# USBFX2LP_4.net
KiCad netlist of a schematic drawn in Altium Designer
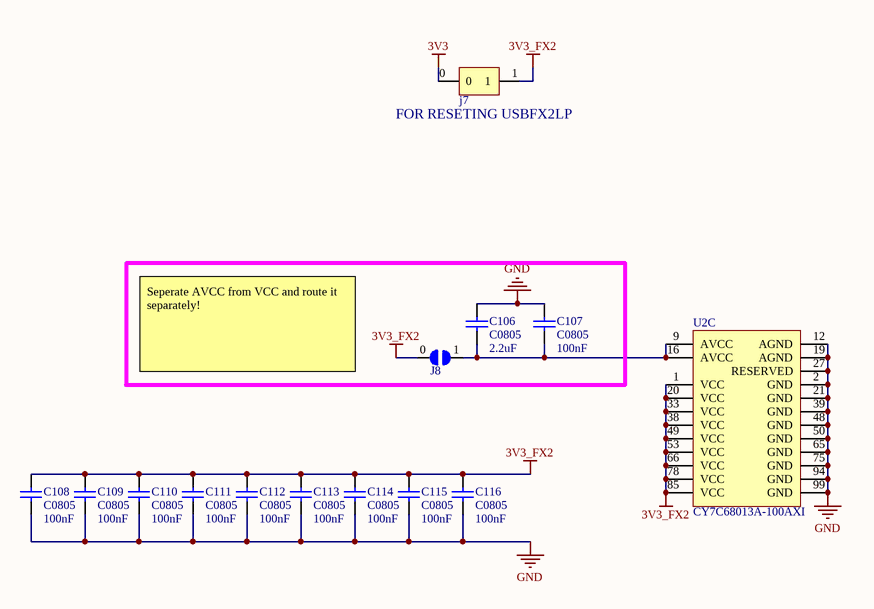
[diagram p0: USBFX2LP_4.SchDoc]

(export (version "E")
  (design (tool "Eeschema 10.0.6"))
  (components
    (comp (ref "C106")
      (value "C0805")
      (footprint "0805")
      (description "Ceramic Chip Capacitor - Standard")
      (fields (field (name "ALTIUM_VALUE") "2.2uF") (field (name "PUBLISHER") "Altium Limited"))
      (libsource (lib "KEMET Chip Capacitor") (part "C0805"))
    )
    (comp (ref "C107")
      (value "C0805")
      (footprint "0805")
      (description "Ceramic Chip Capacitor - Standard")
      (fields (field (name "ALTIUM_VALUE") "100nF") (field (name "PUBLISHER") "Altium Limited"))
      (libsource (lib "KEMET Chip Capacitor") (part "C0805"))
    )
    (comp (ref "C108")
      (value "C0805")
      (footprint "0805")
      (description "Ceramic Chip Capacitor - Standard")
      (fields (field (name "ALTIUM_VALUE") "100nF") (field (name "PUBLISHER") "Altium Limited"))
      (libsource (lib "KEMET Chip Capacitor") (part "C0805"))
    )
    (comp (ref "C109")
      (value "C0805")
      (footprint "0805")
      (description "Ceramic Chip Capacitor - Standard")
      (fields (field (name "ALTIUM_VALUE") "100nF") (field (name "PUBLISHER") "Altium Limited"))
      (libsource (lib "KEMET Chip Capacitor") (part "C0805"))
    )
    (comp (ref "C110")
      (value "C0805")
      (footprint "0805")
      (description "Ceramic Chip Capacitor - Standard")
      (fields (field (name "ALTIUM_VALUE") "100nF") (field (name "PUBLISHER") "Altium Limited"))
      (libsource (lib "KEMET Chip Capacitor") (part "C0805"))
    )
    (comp (ref "C111")
      (value "C0805")
      (footprint "0805")
      (description "Ceramic Chip Capacitor - Standard")
      (fields (field (name "ALTIUM_VALUE") "100nF") (field (name "PUBLISHER") "Altium Limited"))
      (libsource (lib "KEMET Chip Capacitor") (part "C0805"))
    )
    (comp (ref "C112")
      (value "C0805")
      (footprint "0805")
      (description "Ceramic Chip Capacitor - Standard")
      (fields (field (name "ALTIUM_VALUE") "100nF") (field (name "PUBLISHER") "Altium Limited"))
      (libsource (lib "KEMET Chip Capacitor") (part "C0805"))
    )
    (comp (ref "C113")
      (value "C0805")
      (footprint "0805")
      (description "Ceramic Chip Capacitor - Standard")
      (fields (field (name "ALTIUM_VALUE") "100nF") (field (name "PUBLISHER") "Altium Limited"))
      (libsource (lib "KEMET Chip Capacitor") (part "C0805"))
    )
    (comp (ref "C114")
      (value "C0805")
      (footprint "0805")
      (description "Ceramic Chip Capacitor - Standard")
      (fields (field (name "ALTIUM_VALUE") "100nF") (field (name "PUBLISHER") "Altium Limited"))
      (libsource (lib "KEMET Chip Capacitor") (part "C0805"))
    )
    (comp (ref "C115")
      (value "C0805")
      (footprint "0805")
      (description "Ceramic Chip Capacitor - Standard")
      (fields (field (name "ALTIUM_VALUE") "100nF") (field (name "PUBLISHER") "Altium Limited"))
      (libsource (lib "KEMET Chip Capacitor") (part "C0805"))
    )
    (comp (ref "C116")
      (value "C0805")
      (footprint "0805")
      (description "Ceramic Chip Capacitor - Standard")
      (fields (field (name "ALTIUM_VALUE") "100nF") (field (name "PUBLISHER") "Altium Limited"))
      (libsource (lib "KEMET Chip Capacitor") (part "C0805"))
    )
    (comp (ref "j7") (value "2pin") (footprint "2PIN") (libsource (lib "jumper2o54mm") (part "2pin")))
    (comp (ref "J8")
      (value "jumper")
      (footprint "jumper_pcb")
      (libsource (lib "JUMPPER_PRJ") (part "jumper"))
    )
    (comp (ref "U2")
      (value "CY7C68013A-100AXI")
      (footprint "CYP-AX100RA_N")
      (fields (field (name "MANUFACTURER") "Cypress"))
      (libsource (lib "Cypress USB Controllers") (part "CY7C68013A-100AXI"))
    )
  )
  (nets
    (net (code "1") (name "3V3") (class "Default")
      (node (ref "j7") (pin "0") (pinfunction "0_0") (pintype "passive"))
    )
    (net (code "2") (name "3V3_FX2") (class "Default")
      (node (ref "C108") (pin "2") (pinfunction "2_2") (pintype "passive"))
      (node (ref "C109") (pin "2") (pinfunction "2_2") (pintype "passive"))
      (node (ref "C110") (pin "2") (pinfunction "2_2") (pintype "passive"))
      (node (ref "C111") (pin "2") (pinfunction "2_2") (pintype "passive"))
      (node (ref "C112") (pin "2") (pinfunction "2_2") (pintype "passive"))
      (node (ref "C113") (pin "2") (pinfunction "2_2") (pintype "passive"))
      (node (ref "C114") (pin "2") (pinfunction "2_2") (pintype "passive"))
      (node (ref "C115") (pin "2") (pinfunction "2_2") (pintype "passive"))
      (node (ref "C116") (pin "2") (pinfunction "2_2") (pintype "passive"))
      (node (ref "J8") (pin "0") (pintype "passive"))
      (node (ref "U2") (pin "1") (pinfunction "VCC_1") (pintype "power_in"))
      (node (ref "U2") (pin "20") (pinfunction "VCC_20") (pintype "power_in"))
      (node (ref "U2") (pin "33") (pinfunction "VCC_33") (pintype "power_in"))
      (node (ref "U2") (pin "38") (pinfunction "VCC_38") (pintype "power_in"))
      (node (ref "U2") (pin "49") (pinfunction "VCC_49") (pintype "power_in"))
      (node (ref "U2") (pin "53") (pinfunction "VCC_53") (pintype "power_in"))
      (node (ref "U2") (pin "66") (pinfunction "VCC_66") (pintype "power_in"))
      (node (ref "U2") (pin "78") (pinfunction "VCC_78") (pintype "power_in"))
      (node (ref "U2") (pin "85") (pinfunction "VCC_85") (pintype "power_in"))
      (node (ref "j7") (pin "1") (pinfunction "1_1") (pintype "passive"))
    )
    (net (code "3") (name "GND") (class "Default")
      (node (ref "C106") (pin "2") (pinfunction "2_2") (pintype "passive"))
      (node (ref "C107") (pin "2") (pinfunction "2_2") (pintype "passive"))
      (node (ref "C108") (pin "1") (pinfunction "1_1") (pintype "passive"))
      (node (ref "C109") (pin "1") (pinfunction "1_1") (pintype "passive"))
      (node (ref "C110") (pin "1") (pinfunction "1_1") (pintype "passive"))
      (node (ref "C111") (pin "1") (pinfunction "1_1") (pintype "passive"))
      (node (ref "C112") (pin "1") (pinfunction "1_1") (pintype "passive"))
      (node (ref "C113") (pin "1") (pinfunction "1_1") (pintype "passive"))
      (node (ref "C114") (pin "1") (pinfunction "1_1") (pintype "passive"))
      (node (ref "C115") (pin "1") (pinfunction "1_1") (pintype "passive"))
      (node (ref "C116") (pin "1") (pinfunction "1_1") (pintype "passive"))
      (node (ref "U2") (pin "12") (pinfunction "AGND_12") (pintype "power_in"))
      (node (ref "U2") (pin "19") (pinfunction "AGND_19") (pintype "power_in"))
      (node (ref "U2") (pin "2") (pinfunction "GND_2") (pintype "power_in"))
      (node (ref "U2") (pin "21") (pinfunction "GND_21") (pintype "power_in"))
      (node (ref "U2") (pin "27") (pinfunction "RESERVED_27") (pintype "power_in"))
      (node (ref "U2") (pin "39") (pinfunction "GND_39") (pintype "power_in"))
      (node (ref "U2") (pin "48") (pinfunction "GND_48") (pintype "power_in"))
      (node (ref "U2") (pin "50") (pinfunction "GND_50") (pintype "power_in"))
      (node (ref "U2") (pin "65") (pinfunction "GND_65") (pintype "power_in"))
      (node (ref "U2") (pin "75") (pinfunction "GND_75") (pintype "power_in"))
      (node (ref "U2") (pin "94") (pinfunction "GND_94") (pintype "power_in"))
      (node (ref "U2") (pin "99") (pinfunction "GND_99") (pintype "power_in"))
    )
    (net (code "4") (name "Net-(C106-Pad1)") (class "Default")
      (node (ref "C106") (pin "1") (pinfunction "1_1") (pintype "passive"))
      (node (ref "C107") (pin "1") (pinfunction "1_1") (pintype "passive"))
      (node (ref "J8") (pin "1") (pintype "passive"))
      (node (ref "U2") (pin "16") (pinfunction "AVCC_16") (pintype "power_in"))
      (node (ref "U2") (pin "9") (pinfunction "AVCC_9") (pintype "power_in"))
    )
  )
)
